# aamp.net
KiCad netlist of a schematic drawn in EAGLE
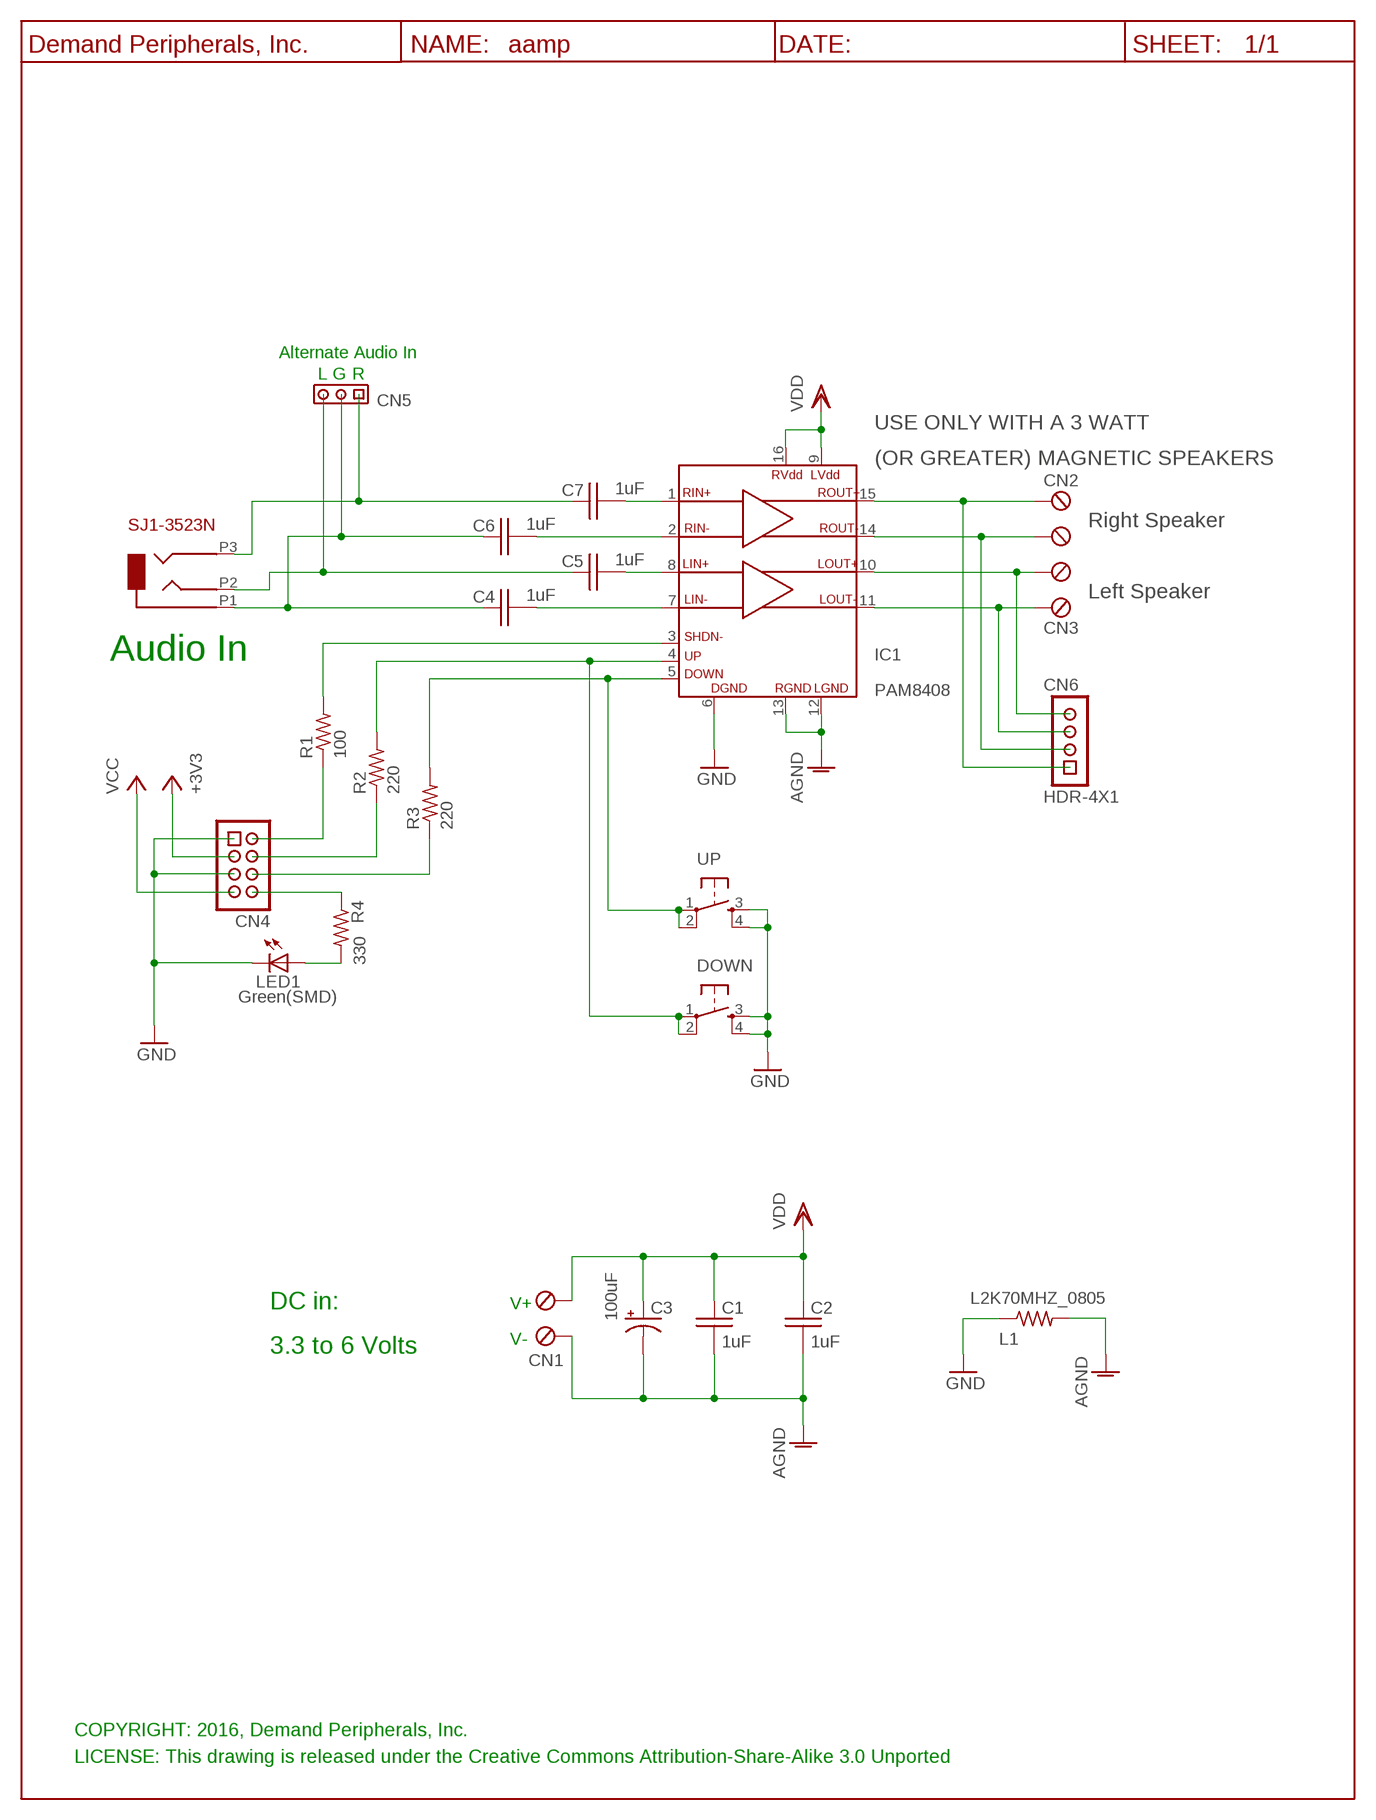
[diagram p0: schematic, sheet 1]

(export (version "E")
  (design (tool "Eeschema 10.0.6"))
  (components
    (comp (ref "AUDIN")
      (value "SJ1-3523N")
      (footprint "eagle-import:CUI-SJ1-3523N")
      (libsource (lib "eagle-import") (part "SJ1-3523N"))
    )
    (comp (ref "C1")
      (value "1uF")
      (footprint "eagle-import:C0603")
      (libsource (lib "eagle-import") (part "C1.0UF_C0603"))
    )
    (comp (ref "C2")
      (value "1uF")
      (footprint "eagle-import:C0603")
      (libsource (lib "eagle-import") (part "C1.0UF_C0603"))
    )
    (comp (ref "C3")
      (value "100uF")
      (footprint "eagle-import:E3.5-8")
      (libsource (lib "eagle-import") (part "C100UF_E3.5-8"))
    )
    (comp (ref "C4")
      (value "1uF")
      (footprint "eagle-import:C0603")
      (libsource (lib "eagle-import") (part "C1.0UF_C0603"))
    )
    (comp (ref "C5")
      (value "1uF")
      (footprint "eagle-import:C0603")
      (libsource (lib "eagle-import") (part "C1.0UF_C0603"))
    )
    (comp (ref "C6")
      (value "1uF")
      (footprint "eagle-import:C0603")
      (libsource (lib "eagle-import") (part "C1.0UF_C0603"))
    )
    (comp (ref "C7")
      (value "1uF")
      (footprint "eagle-import:C0603")
      (libsource (lib "eagle-import") (part "C1.0UF_C0603"))
    )
    (comp (ref "CN1")
      (value "TBLK-5.08-X2")
      (footprint "eagle-import:TBLK-5.08-X2")
      (libsource (lib "eagle-import") (part "TBLK-5.08-X2"))
    )
    (comp (ref "CN2")
      (value "TBLK-5.08-X2")
      (footprint "eagle-import:TBLK-5.08-X2")
      (libsource (lib "eagle-import") (part "TBLK-5.08-X2"))
    )
    (comp (ref "CN3")
      (value "TBLK-5.08-X2")
      (footprint "eagle-import:TBLK-5.08-X2")
      (libsource (lib "eagle-import") (part "TBLK-5.08-X2"))
    )
    (comp (ref "CN4")
      (value "HDR-4X2-SHR")
      (footprint "eagle-import:HDR-4X2")
      (libsource (lib "eagle-import") (part "HDR-4X2-SHR"))
    )
    (comp (ref "CN5")
      (value "HDR-3X1")
      (footprint "eagle-import:HDR-3X1")
      (libsource (lib "eagle-import") (part "HDR-3X1"))
    )
    (comp (ref "CN6")
      (value "HDR-4X1")
      (footprint "eagle-import:HDR-4X1")
      (libsource (lib "eagle-import") (part "HDR-4X1"))
    )
    (comp (ref "DOWN")
      (value "DTSM-6")
      (footprint "eagle-import:DTSM-6")
      (libsource (lib "eagle-import") (part "DTSM-6"))
    )
    (comp (ref "FRM1")
      (value "DP_FRAME_P")
      (footprint "eagle-import:P_FRAME")
      (libsource (lib "eagle-import") (part "DP_FRAME_P"))
    )
    (comp (ref "IC1")
      (value "PAM8408")
      (footprint "eagle-import:SO16")
      (libsource (lib "eagle-import") (part "PAM8408"))
    )
    (comp (ref "L1")
      (value "L2K70MHZ_0805")
      (footprint "eagle-import:R0805")
      (libsource (lib "eagle-import") (part "L2K70MHZR0805"))
    )
    (comp (ref "LED1")
      (value "Green(SMD)")
      (footprint "eagle-import:0603")
      (libsource (lib "eagle-import") (part "LED-0603-GRN"))
    )
    (comp (ref "R1")
      (value "100")
      (footprint "eagle-import:R0603")
      (libsource (lib "eagle-import") (part "R100_R0603"))
    )
    (comp (ref "R2")
      (value "220")
      (footprint "eagle-import:R0603")
      (libsource (lib "eagle-import") (part "R220_R0603"))
    )
    (comp (ref "R3")
      (value "220")
      (footprint "eagle-import:R0603")
      (libsource (lib "eagle-import") (part "R220_R0603"))
    )
    (comp (ref "R4")
      (value "330")
      (footprint "eagle-import:R0603")
      (libsource (lib "eagle-import") (part "R330_R0603"))
    )
    (comp (ref "UP")
      (value "DTSM-6")
      (footprint "eagle-import:DTSM-6")
      (libsource (lib "eagle-import") (part "DTSM-6"))
    )
  )
  (nets
    (net (code "1") (name "+3V3") (class "Default")
      (node (ref "CN4") (pin "3") (pinfunction "3_3") (pintype "passive"))
    )
    (net (code "2") (name "AGND") (class "Default")
      (node (ref "C1") (pin "2") (pinfunction "2_2") (pintype "passive"))
      (node (ref "C2") (pin "2") (pinfunction "2_2") (pintype "passive"))
      (node (ref "C3") (pin "-") (pinfunction "-_-") (pintype "passive"))
      (node (ref "CN1") (pin "1") (pinfunction "KL_1") (pintype "passive"))
      (node (ref "IC1") (pin "12") (pinfunction "LGND_12") (pintype "power_in"))
      (node (ref "IC1") (pin "13") (pinfunction "RGND_13") (pintype "power_in"))
      (node (ref "L1") (pin "2") (pinfunction "2_2") (pintype "passive"))
    )
    (net (code "3") (name "GND") (class "Default")
      (node (ref "CN4") (pin "1") (pinfunction "1_1") (pintype "passive"))
      (node (ref "CN4") (pin "5") (pinfunction "5_5") (pintype "passive"))
      (node (ref "DOWN") (pin "3") (pinfunction "3_3") (pintype "passive"))
      (node (ref "DOWN") (pin "4") (pinfunction "4_4") (pintype "passive"))
      (node (ref "IC1") (pin "6") (pinfunction "GND_6") (pintype "power_in"))
      (node (ref "L1") (pin "1") (pinfunction "1_1") (pintype "passive"))
      (node (ref "LED1") (pin "C") (pinfunction "C_C") (pintype "passive"))
      (node (ref "UP") (pin "3") (pinfunction "3_3") (pintype "passive"))
      (node (ref "UP") (pin "4") (pinfunction "4_4") (pintype "passive"))
    )
    (net (code "4") (name "Net-(AUDIN-1)") (class "Default")
      (node (ref "AUDIN") (pin "P1") (pinfunction "1_P1") (pintype "passive"))
      (node (ref "C4") (pin "1") (pinfunction "1_1") (pintype "passive"))
      (node (ref "C6") (pin "1") (pinfunction "1_1") (pintype "passive"))
      (node (ref "CN5") (pin "2") (pinfunction "2_2") (pintype "passive"))
    )
    (net (code "5") (name "Net-(AUDIN-2)") (class "Default")
      (node (ref "AUDIN") (pin "P2") (pinfunction "2_P2") (pintype "passive"))
      (node (ref "C5") (pin "1") (pinfunction "1_1") (pintype "passive"))
      (node (ref "CN5") (pin "3") (pinfunction "3_3") (pintype "passive"))
    )
    (net (code "6") (name "Net-(AUDIN-3)") (class "Default")
      (node (ref "AUDIN") (pin "P3") (pinfunction "3_P3") (pintype "passive"))
      (node (ref "C7") (pin "1") (pinfunction "1_1") (pintype "passive"))
      (node (ref "CN5") (pin "1") (pinfunction "1_1") (pintype "passive"))
    )
    (net (code "7") (name "Net-(CN2-KL)") (class "Default")
      (node (ref "CN2") (pin "1") (pinfunction "KL_1") (pintype "passive"))
      (node (ref "CN6") (pin "2") (pinfunction "2_2") (pintype "passive"))
      (node (ref "IC1") (pin "14") (pinfunction "ROUT-_14") (pintype "output"))
    )
    (net (code "8") (name "Net-(CN2-KL1)") (class "Default")
      (node (ref "CN2") (pin "2") (pinfunction "KL1_2") (pintype "passive"))
      (node (ref "CN6") (pin "1") (pinfunction "1_1") (pintype "passive"))
      (node (ref "IC1") (pin "15") (pinfunction "ROUT+_15") (pintype "output"))
    )
    (net (code "9") (name "Net-(CN3-KL)") (class "Default")
      (node (ref "CN3") (pin "1") (pinfunction "KL_1") (pintype "passive"))
      (node (ref "CN6") (pin "4") (pinfunction "4_4") (pintype "passive"))
      (node (ref "IC1") (pin "10") (pinfunction "LOUT+_10") (pintype "output"))
    )
    (net (code "10") (name "Net-(CN3-KL1)") (class "Default")
      (node (ref "CN3") (pin "2") (pinfunction "KL1_2") (pintype "passive"))
      (node (ref "CN6") (pin "3") (pinfunction "3_3") (pintype "passive"))
      (node (ref "IC1") (pin "11") (pinfunction "LOUT-_11") (pintype "output"))
    )
    (net (code "11") (name "Net-(CN4-Pad2)") (class "Default")
      (node (ref "CN4") (pin "2") (pinfunction "2_2") (pintype "passive"))
      (node (ref "R1") (pin "1") (pinfunction "1_1") (pintype "passive"))
    )
    (net (code "12") (name "Net-(CN4-Pad4)") (class "Default")
      (node (ref "CN4") (pin "4") (pinfunction "4_4") (pintype "passive"))
      (node (ref "R2") (pin "1") (pinfunction "1_1") (pintype "passive"))
    )
    (net (code "13") (name "Net-(CN4-Pad6)") (class "Default")
      (node (ref "CN4") (pin "6") (pinfunction "6_6") (pintype "passive"))
      (node (ref "R3") (pin "1") (pinfunction "1_1") (pintype "passive"))
    )
    (net (code "14") (name "Net-(CN4-Pad8)") (class "Default")
      (node (ref "CN4") (pin "8") (pinfunction "8_8") (pintype "passive"))
      (node (ref "R4") (pin "1") (pinfunction "1_1") (pintype "passive"))
    )
    (net (code "15") (name "Net-(IC1-DOWN)") (class "Default")
      (node (ref "IC1") (pin "5") (pinfunction "DOWN_5") (pintype "input"))
      (node (ref "R3") (pin "2") (pinfunction "2_2") (pintype "passive"))
      (node (ref "UP") (pin "1") (pinfunction "1_1") (pintype "passive"))
      (node (ref "UP") (pin "2") (pinfunction "2_2") (pintype "passive"))
    )
    (net (code "16") (name "Net-(IC1-LIN+)") (class "Default")
      (node (ref "C5") (pin "2") (pinfunction "2_2") (pintype "passive"))
      (node (ref "IC1") (pin "8") (pinfunction "LIN+_8") (pintype "input"))
    )
    (net (code "17") (name "Net-(IC1-LIN-)") (class "Default")
      (node (ref "C4") (pin "2") (pinfunction "2_2") (pintype "passive"))
      (node (ref "IC1") (pin "7") (pinfunction "LIN-_7") (pintype "input"))
    )
    (net (code "18") (name "Net-(IC1-RIN+)") (class "Default")
      (node (ref "C7") (pin "2") (pinfunction "2_2") (pintype "passive"))
      (node (ref "IC1") (pin "1") (pinfunction "RIN+_1") (pintype "input"))
    )
    (net (code "19") (name "Net-(IC1-RIN-)") (class "Default")
      (node (ref "C6") (pin "2") (pinfunction "2_2") (pintype "passive"))
      (node (ref "IC1") (pin "2") (pinfunction "RIN-_2") (pintype "input"))
    )
    (net (code "20") (name "Net-(IC1-SHDN-)") (class "Default")
      (node (ref "IC1") (pin "3") (pinfunction "SHDN-_3") (pintype "bidirectional"))
      (node (ref "R1") (pin "2") (pinfunction "2_2") (pintype "passive"))
    )
    (net (code "21") (name "Net-(IC1-UP)") (class "Default")
      (node (ref "DOWN") (pin "1") (pinfunction "1_1") (pintype "passive"))
      (node (ref "DOWN") (pin "2") (pinfunction "2_2") (pintype "passive"))
      (node (ref "IC1") (pin "4") (pinfunction "UP_4") (pintype "input"))
      (node (ref "R2") (pin "2") (pinfunction "2_2") (pintype "passive"))
    )
    (net (code "22") (name "Net-(LED1-PadA)") (class "Default")
      (node (ref "LED1") (pin "A") (pinfunction "A_A") (pintype "passive"))
      (node (ref "R4") (pin "2") (pinfunction "2_2") (pintype "passive"))
    )
    (net (code "23") (name "VCC") (class "Default")
      (node (ref "CN4") (pin "7") (pinfunction "7_7") (pintype "passive"))
    )
    (net (code "24") (name "VDD") (class "Default")
      (node (ref "C1") (pin "1") (pinfunction "1_1") (pintype "passive"))
      (node (ref "C2") (pin "1") (pinfunction "1_1") (pintype "passive"))
      (node (ref "C3") (pin "+") (pinfunction "+_+") (pintype "passive"))
      (node (ref "CN1") (pin "2") (pinfunction "KL1_2") (pintype "passive"))
      (node (ref "IC1") (pin "16") (pinfunction "RVDD_16") (pintype "power_in"))
      (node (ref "IC1") (pin "9") (pinfunction "LVDD_9") (pintype "power_in"))
    )
  )
)
